# schematic_master.net
KiCad netlist of a schematic drawn in EAGLE
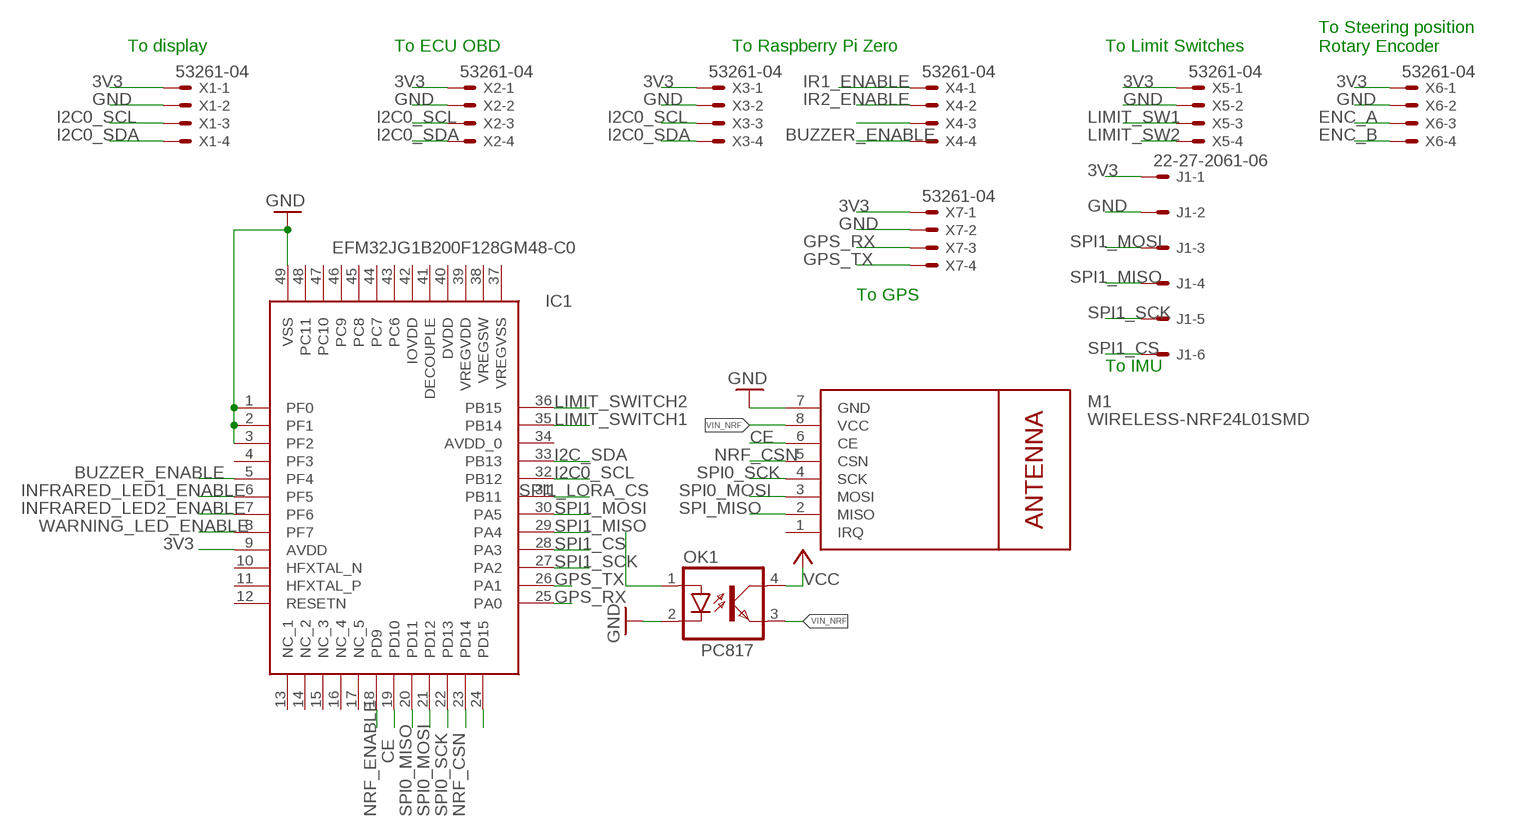
[diagram p0: schematic, sheet 1]

(export (version "E")
  (design (tool "Eeschema 10.0.6"))
  (components
    (comp (ref "IC1")
      (value "EFM32JG1B200F128GM48-C0")
      (footprint "eagle-import:QFN50P700X700X90-49N")
      (fields (field (name "MOUSER_PART_NUMBER") "634-JG1B200F128GM48C"))
      (libsource (lib "eagle-import") (part "EFM32JG1B200F128GM48-C0"))
    )
    (comp (ref "J1")
      (value "22-27-2061-06")
      (footprint "eagle-import:6410-06")
      (fields (field (name "MF") "MOLEX"))
      (libsource (lib "eagle-import") (part "22-?-0627-2061"))
    )
    (comp (ref "M1")
      (value "WIRELESS-NRF24L01SMD")
      (footprint "eagle-import:WIRELESS-NRF24L01-SMD")
      (libsource (lib "eagle-import") (part "WIRELESS-NRF24L01SMD"))
    )
    (comp (ref "OK1")
      (value "PC817")
      (footprint "eagle-import:DIL04")
      (fields (field (name "MPN") "PC817X4J000F"))
      (libsource (lib "eagle-import") (part "PC817"))
    )
    (comp (ref "X1")
      (value "53261-04")
      (footprint "eagle-import:53261-04")
      (fields (field (name "MF") "MOLEX"))
      (libsource (lib "eagle-import") (part "53?-04261"))
    )
    (comp (ref "X2")
      (value "53261-04")
      (footprint "eagle-import:53261-04")
      (fields (field (name "MF") "MOLEX"))
      (libsource (lib "eagle-import") (part "53?-04261"))
    )
    (comp (ref "X3")
      (value "53261-04")
      (footprint "eagle-import:53261-04")
      (fields (field (name "MF") "MOLEX"))
      (libsource (lib "eagle-import") (part "53?-04261"))
    )
    (comp (ref "X4")
      (value "53261-04")
      (footprint "eagle-import:53261-04")
      (fields (field (name "MF") "MOLEX"))
      (libsource (lib "eagle-import") (part "53?-04261"))
    )
    (comp (ref "X5")
      (value "53261-04")
      (footprint "eagle-import:53261-04")
      (fields (field (name "MF") "MOLEX"))
      (libsource (lib "eagle-import") (part "53?-04261"))
    )
    (comp (ref "X6")
      (value "53261-04")
      (footprint "eagle-import:53261-04")
      (fields (field (name "MF") "MOLEX"))
      (libsource (lib "eagle-import") (part "53?-04261"))
    )
    (comp (ref "X7")
      (value "53261-04")
      (footprint "eagle-import:53261-04")
      (fields (field (name "MF") "MOLEX"))
      (libsource (lib "eagle-import") (part "53?-04261"))
    )
  )
  (nets
    (net (code "1") (name "/3V3") (class "Default")
      (node (ref "IC1") (pin "9") (pinfunction "AVDD_9") (pintype "bidirectional"))
      (node (ref "J1") (pin "1") (pinfunction "S_1") (pintype "passive"))
      (node (ref "X1") (pin "1") (pinfunction "S_1") (pintype "passive"))
      (node (ref "X2") (pin "1") (pinfunction "S_1") (pintype "passive"))
      (node (ref "X3") (pin "1") (pinfunction "S_1") (pintype "passive"))
      (node (ref "X5") (pin "1") (pinfunction "S_1") (pintype "passive"))
      (node (ref "X6") (pin "1") (pinfunction "S_1") (pintype "passive"))
      (node (ref "X7") (pin "1") (pinfunction "S_1") (pintype "passive"))
    )
    (net (code "2") (name "/BUZZER_ENABLE") (class "Default")
      (node (ref "IC1") (pin "5") (pinfunction "PF4_5") (pintype "bidirectional"))
      (node (ref "X4") (pin "3") (pinfunction "S_3") (pintype "passive"))
    )
    (net (code "3") (name "/CE") (class "Default")
      (node (ref "IC1") (pin "19") (pinfunction "PD10_19") (pintype "bidirectional"))
      (node (ref "M1") (pin "6") (pinfunction "CE_6") (pintype "bidirectional"))
    )
    (net (code "4") (name "/ENC_A") (class "Default")
      (node (ref "X6") (pin "3") (pinfunction "S_3") (pintype "passive"))
    )
    (net (code "5") (name "/ENC_B") (class "Default")
      (node (ref "X6") (pin "4") (pinfunction "S_4") (pintype "passive"))
    )
    (net (code "6") (name "/GPS_RX") (class "Default")
      (node (ref "IC1") (pin "25") (pinfunction "PA0_25") (pintype "bidirectional"))
      (node (ref "X7") (pin "3") (pinfunction "S_3") (pintype "passive"))
    )
    (net (code "7") (name "/GPS_TX") (class "Default")
      (node (ref "IC1") (pin "26") (pinfunction "PA1_26") (pintype "bidirectional"))
      (node (ref "X7") (pin "4") (pinfunction "S_4") (pintype "passive"))
    )
    (net (code "8") (name "/I2C0_SCL") (class "Default")
      (node (ref "IC1") (pin "32") (pinfunction "PB12_32") (pintype "bidirectional"))
      (node (ref "X1") (pin "3") (pinfunction "S_3") (pintype "passive"))
      (node (ref "X2") (pin "3") (pinfunction "S_3") (pintype "passive"))
      (node (ref "X3") (pin "3") (pinfunction "S_3") (pintype "passive"))
    )
    (net (code "9") (name "/I2C0_SDA") (class "Default")
      (node (ref "X1") (pin "4") (pinfunction "S_4") (pintype "passive"))
      (node (ref "X2") (pin "4") (pinfunction "S_4") (pintype "passive"))
      (node (ref "X3") (pin "4") (pinfunction "S_4") (pintype "passive"))
    )
    (net (code "10") (name "/I2C_SDA") (class "Default")
      (node (ref "IC1") (pin "33") (pinfunction "PB13_33") (pintype "bidirectional"))
    )
    (net (code "11") (name "/INFRARED_LED1_ENABLE") (class "Default")
      (node (ref "IC1") (pin "6") (pinfunction "PF5_6") (pintype "bidirectional"))
    )
    (net (code "12") (name "/INFRARED_LED2_ENABLE") (class "Default")
      (node (ref "IC1") (pin "7") (pinfunction "PF6_7") (pintype "bidirectional"))
    )
    (net (code "13") (name "/IR1_ENABLE") (class "Default")
      (node (ref "X4") (pin "1") (pinfunction "S_1") (pintype "passive"))
    )
    (net (code "14") (name "/IR2_ENABLE") (class "Default")
      (node (ref "X4") (pin "2") (pinfunction "S_2") (pintype "passive"))
    )
    (net (code "15") (name "/LIMIT_SW1") (class "Default")
      (node (ref "X5") (pin "3") (pinfunction "S_3") (pintype "passive"))
    )
    (net (code "16") (name "/LIMIT_SW2") (class "Default")
      (node (ref "X5") (pin "4") (pinfunction "S_4") (pintype "passive"))
    )
    (net (code "17") (name "/LIMIT_SWITCH1") (class "Default")
      (node (ref "IC1") (pin "35") (pinfunction "PB14_35") (pintype "bidirectional"))
    )
    (net (code "18") (name "/LIMIT_SWITCH2") (class "Default")
      (node (ref "IC1") (pin "36") (pinfunction "PB15_36") (pintype "bidirectional"))
    )
    (net (code "19") (name "/NRF_CSN") (class "Default")
      (node (ref "IC1") (pin "23") (pinfunction "PD14_23") (pintype "bidirectional"))
      (node (ref "M1") (pin "5") (pinfunction "CSN_5") (pintype "bidirectional"))
    )
    (net (code "20") (name "/NRF_ENABLE") (class "Default")
      (node (ref "IC1") (pin "18") (pinfunction "PD9_18") (pintype "bidirectional"))
    )
    (net (code "21") (name "/SPI0_MISO") (class "Default")
      (node (ref "IC1") (pin "20") (pinfunction "PD11_20") (pintype "bidirectional"))
    )
    (net (code "22") (name "/SPI0_MOSI") (class "Default")
      (node (ref "IC1") (pin "21") (pinfunction "PD12_21") (pintype "bidirectional"))
      (node (ref "M1") (pin "3") (pinfunction "MOSI_3") (pintype "bidirectional"))
    )
    (net (code "23") (name "/SPI0_SCK") (class "Default")
      (node (ref "IC1") (pin "22") (pinfunction "PD13_22") (pintype "bidirectional"))
      (node (ref "M1") (pin "4") (pinfunction "SCK_4") (pintype "bidirectional"))
    )
    (net (code "24") (name "/SPI1_CS") (class "Default")
      (node (ref "IC1") (pin "28") (pinfunction "PA3_28") (pintype "bidirectional"))
      (node (ref "J1") (pin "6") (pinfunction "S_6") (pintype "passive"))
    )
    (net (code "25") (name "/SPI1_LORA_CS") (class "Default")
      (node (ref "IC1") (pin "31") (pinfunction "PB11_31") (pintype "bidirectional"))
    )
    (net (code "26") (name "/SPI1_MISO") (class "Default")
      (node (ref "IC1") (pin "29") (pinfunction "PA4_29") (pintype "bidirectional"))
      (node (ref "J1") (pin "4") (pinfunction "S_4") (pintype "passive"))
    )
    (net (code "27") (name "/SPI1_MOSI") (class "Default")
      (node (ref "IC1") (pin "30") (pinfunction "PA5_30") (pintype "bidirectional"))
      (node (ref "J1") (pin "3") (pinfunction "S_3") (pintype "passive"))
    )
    (net (code "28") (name "/SPI1_SCK") (class "Default")
      (node (ref "IC1") (pin "27") (pinfunction "PA2_27") (pintype "bidirectional"))
      (node (ref "J1") (pin "5") (pinfunction "S_5") (pintype "passive"))
    )
    (net (code "29") (name "/SPI_MISO") (class "Default")
      (node (ref "M1") (pin "2") (pinfunction "MISO_2") (pintype "bidirectional"))
    )
    (net (code "30") (name "/WARNING_LED_ENABLE") (class "Default")
      (node (ref "IC1") (pin "8") (pinfunction "PF7_8") (pintype "bidirectional"))
    )
    (net (code "31") (name "GND") (class "Default")
      (node (ref "IC1") (pin "1") (pinfunction "PF0_1") (pintype "bidirectional"))
      (node (ref "IC1") (pin "2") (pinfunction "PF1_2") (pintype "bidirectional"))
      (node (ref "IC1") (pin "3") (pinfunction "PF2_3") (pintype "bidirectional"))
      (node (ref "IC1") (pin "49") (pinfunction "VSS_49") (pintype "bidirectional"))
      (node (ref "J1") (pin "2") (pinfunction "S_2") (pintype "passive"))
      (node (ref "M1") (pin "7") (pinfunction "GND_7") (pintype "power_in"))
      (node (ref "OK1") (pin "2") (pinfunction "C_2") (pintype "passive"))
      (node (ref "X1") (pin "2") (pinfunction "S_2") (pintype "passive"))
      (node (ref "X2") (pin "2") (pinfunction "S_2") (pintype "passive"))
      (node (ref "X3") (pin "2") (pinfunction "S_2") (pintype "passive"))
      (node (ref "X5") (pin "2") (pinfunction "S_2") (pintype "passive"))
      (node (ref "X6") (pin "2") (pinfunction "S_2") (pintype "passive"))
      (node (ref "X7") (pin "2") (pinfunction "S_2") (pintype "passive"))
    )
    (net (code "32") (name "VCC") (class "Default")
      (node (ref "OK1") (pin "4") (pinfunction "COL_4") (pintype "passive"))
    )
    (net (code "33") (name "VIN_NRF") (class "Default")
      (node (ref "M1") (pin "8") (pinfunction "VCC_8") (pintype "power_in"))
      (node (ref "OK1") (pin "3") (pinfunction "EMIT_3") (pintype "passive"))
    )
    (net (code "34") (name "unconnected-(IC1-AVDD_0-Pad34)") (class "Default")
      (node (ref "IC1") (pin "34") (pinfunction "AVDD_0_34") (pintype "bidirectional"))
    )
    (net (code "35") (name "unconnected-(IC1-DECOUPLE-Pad41)") (class "Default")
      (node (ref "IC1") (pin "41") (pinfunction "DECOUPLE_41") (pintype "bidirectional"))
    )
    (net (code "36") (name "unconnected-(IC1-DVDD-Pad40)") (class "Default")
      (node (ref "IC1") (pin "40") (pinfunction "DVDD_40") (pintype "bidirectional"))
    )
    (net (code "37") (name "unconnected-(IC1-HFXTAL_N-Pad10)") (class "Default")
      (node (ref "IC1") (pin "10") (pinfunction "HFXTAL_N_10") (pintype "bidirectional"))
    )
    (net (code "38") (name "unconnected-(IC1-HFXTAL_P-Pad11)") (class "Default")
      (node (ref "IC1") (pin "11") (pinfunction "HFXTAL_P_11") (pintype "bidirectional"))
    )
    (net (code "39") (name "unconnected-(IC1-IOVDD-Pad42)") (class "Default")
      (node (ref "IC1") (pin "42") (pinfunction "IOVDD_42") (pintype "bidirectional"))
    )
    (net (code "40") (name "unconnected-(IC1-NC_1-Pad13)") (class "Default")
      (node (ref "IC1") (pin "13") (pinfunction "NC_1_13") (pintype "bidirectional"))
    )
    (net (code "41") (name "unconnected-(IC1-NC_2-Pad14)") (class "Default")
      (node (ref "IC1") (pin "14") (pinfunction "NC_2_14") (pintype "bidirectional"))
    )
    (net (code "42") (name "unconnected-(IC1-NC_3-Pad15)") (class "Default")
      (node (ref "IC1") (pin "15") (pinfunction "NC_3_15") (pintype "bidirectional"))
    )
    (net (code "43") (name "unconnected-(IC1-NC_4-Pad16)") (class "Default")
      (node (ref "IC1") (pin "16") (pinfunction "NC_4_16") (pintype "bidirectional"))
    )
    (net (code "44") (name "unconnected-(IC1-NC_5-Pad17)") (class "Default")
      (node (ref "IC1") (pin "17") (pinfunction "NC_5_17") (pintype "bidirectional"))
    )
    (net (code "45") (name "unconnected-(IC1-PC6-Pad43)") (class "Default")
      (node (ref "IC1") (pin "43") (pinfunction "PC6_43") (pintype "bidirectional"))
    )
    (net (code "46") (name "unconnected-(IC1-PC7-Pad44)") (class "Default")
      (node (ref "IC1") (pin "44") (pinfunction "PC7_44") (pintype "bidirectional"))
    )
    (net (code "47") (name "unconnected-(IC1-PC8-Pad45)") (class "Default")
      (node (ref "IC1") (pin "45") (pinfunction "PC8_45") (pintype "bidirectional"))
    )
    (net (code "48") (name "unconnected-(IC1-PC9-Pad46)") (class "Default")
      (node (ref "IC1") (pin "46") (pinfunction "PC9_46") (pintype "bidirectional"))
    )
    (net (code "49") (name "unconnected-(IC1-PC10-Pad47)") (class "Default")
      (node (ref "IC1") (pin "47") (pinfunction "PC10_47") (pintype "bidirectional"))
    )
    (net (code "50") (name "unconnected-(IC1-PC11-Pad48)") (class "Default")
      (node (ref "IC1") (pin "48") (pinfunction "PC11_48") (pintype "bidirectional"))
    )
    (net (code "51") (name "unconnected-(IC1-PD15-Pad24)") (class "Default")
      (node (ref "IC1") (pin "24") (pinfunction "PD15_24") (pintype "bidirectional"))
    )
    (net (code "52") (name "unconnected-(IC1-PF3-Pad4)") (class "Default")
      (node (ref "IC1") (pin "4") (pinfunction "PF3_4") (pintype "bidirectional"))
    )
    (net (code "53") (name "unconnected-(IC1-RESETN-Pad12)") (class "Default")
      (node (ref "IC1") (pin "12") (pinfunction "RESETN_12") (pintype "bidirectional"))
    )
    (net (code "54") (name "unconnected-(IC1-VREGSW-Pad38)") (class "Default")
      (node (ref "IC1") (pin "38") (pinfunction "VREGSW_38") (pintype "bidirectional"))
    )
    (net (code "55") (name "unconnected-(IC1-VREGVDD-Pad39)") (class "Default")
      (node (ref "IC1") (pin "39") (pinfunction "VREGVDD_39") (pintype "bidirectional"))
    )
    (net (code "56") (name "unconnected-(IC1-VREGVSS-Pad37)") (class "Default")
      (node (ref "IC1") (pin "37") (pinfunction "VREGVSS_37") (pintype "bidirectional"))
    )
    (net (code "57") (name "unconnected-(M1-IRQ-Pad1)") (class "Default")
      (node (ref "M1") (pin "1") (pinfunction "IRQ_1") (pintype "bidirectional"))
    )
    (net (code "58") (name "unconnected-(OK1-A-Pad1)") (class "Default")
      (node (ref "OK1") (pin "1") (pinfunction "A_1") (pintype "passive"))
    )
    (net (code "59") (name "unconnected-(X4D-S-Pad4)") (class "Default")
      (node (ref "X4") (pin "4") (pinfunction "S_4") (pintype "passive"))
    )
  )
)
